# bmsMaster_usb.net
KiCad netlist of a schematic drawn in Altium Designer
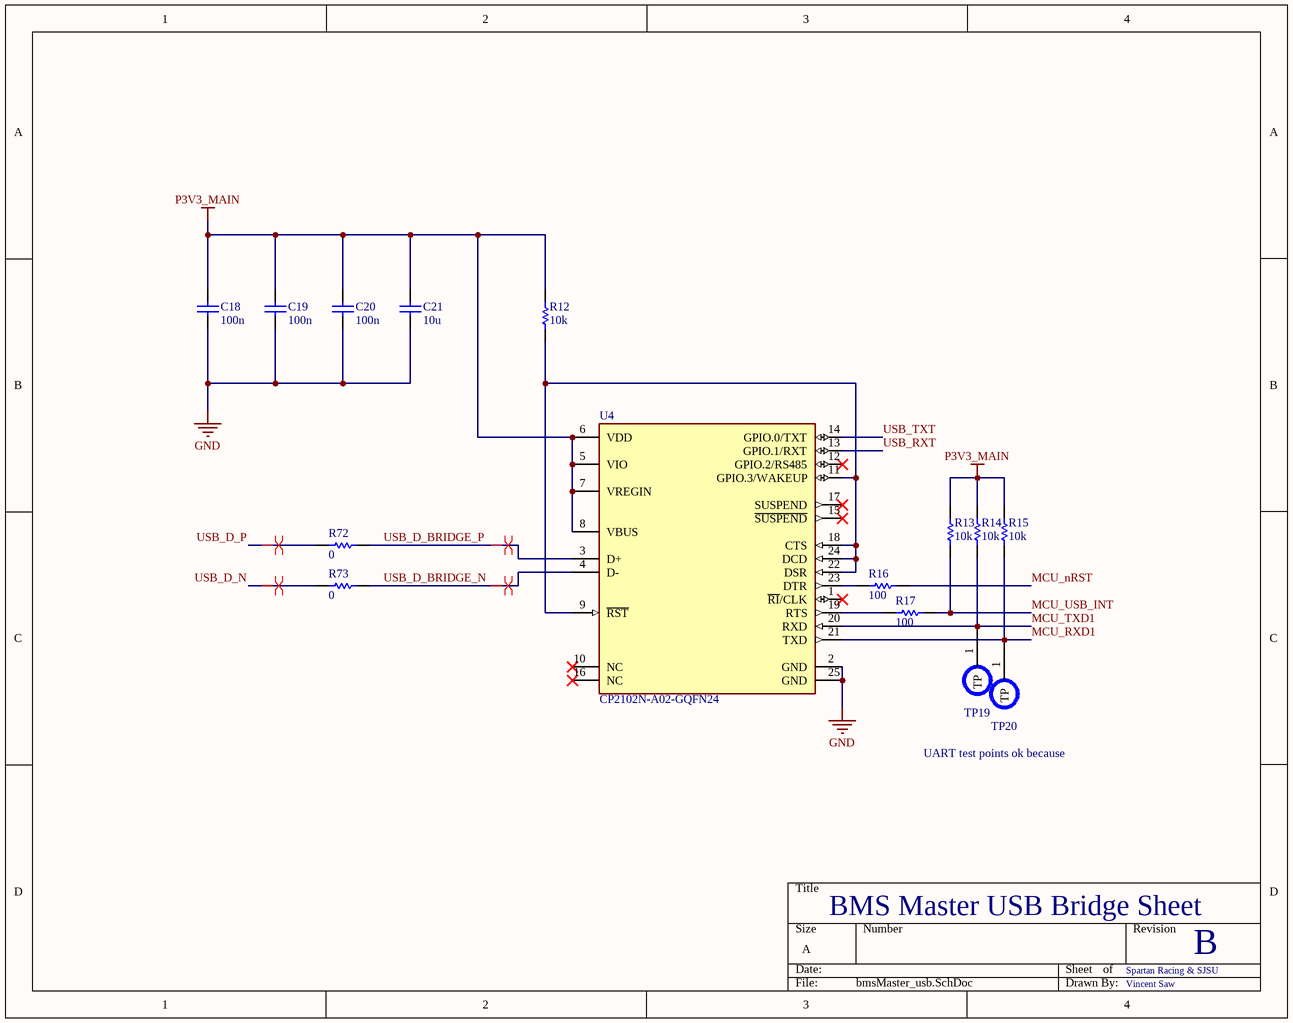
[diagram p0: bmsMaster_usb.SchDoc]

(export (version "E")
  (design (tool "Eeschema 10.0.6"))
  (components
    (comp (ref "C18")
      (value "100n")
      (footprint "CAPC1608X90N")
      (description "Capacitor")
      (libsource (lib "Simulation Generic Components") (part "Capacitor"))
    )
    (comp (ref "C19")
      (value "100n")
      (footprint "CAPC1608X90N")
      (description "Capacitor")
      (libsource (lib "Simulation Generic Components") (part "Capacitor"))
    )
    (comp (ref "C20")
      (value "100n")
      (footprint "CAPC1608X90N")
      (description "Capacitor")
      (libsource (lib "Simulation Generic Components") (part "Capacitor"))
    )
    (comp (ref "C21")
      (value "10u")
      (footprint "CAPC1608X90N")
      (description "Capacitor")
      (libsource (lib "Simulation Generic Components") (part "Capacitor"))
    )
    (comp (ref "R12")
      (value "10k")
      (footprint "RESC1608X50N")
      (description "Resistor")
      (libsource (lib "Simulation Generic Components") (part "Resistor"))
    )
    (comp (ref "R13")
      (value "10k")
      (footprint "RESC1608X50N")
      (description "Resistor")
      (libsource (lib "Simulation Generic Components") (part "Resistor"))
    )
    (comp (ref "R14")
      (value "10k")
      (footprint "RESC1608X50N")
      (description "Resistor")
      (libsource (lib "Simulation Generic Components") (part "Resistor"))
    )
    (comp (ref "R15")
      (value "10k")
      (footprint "RESC1608X50N")
      (description "Resistor")
      (libsource (lib "Simulation Generic Components") (part "Resistor"))
    )
    (comp (ref "R16")
      (value "100")
      (footprint "RESC1608X50N")
      (description "Resistor")
      (libsource (lib "Simulation Generic Components") (part "Resistor"))
    )
    (comp (ref "R17")
      (value "100")
      (footprint "RESC1608X50N")
      (description "Resistor")
      (libsource (lib "Simulation Generic Components") (part "Resistor"))
    )
    (comp (ref "R72")
      (value "0")
      (footprint "RESC1608X50N")
      (description "Resistor")
      (libsource (lib "Simulation Generic Components") (part "Resistor"))
    )
    (comp (ref "R73")
      (value "0")
      (footprint "RESC1608X50N")
      (description "Resistor")
      (libsource (lib "Simulation Generic Components") (part "Resistor"))
    )
    (comp (ref "TP19")
      (value "TSTPT")
      (footprint "Testpoint1")
      (libsource (lib "testpoint1") (part "Testpoint1"))
    )
    (comp (ref "TP20")
      (value "TSTPT")
      (footprint "Testpoint1")
      (libsource (lib "testpoint1") (part "Testpoint1"))
    )
    (comp (ref "U4")
      (value "CP2102N-A02-GQFN24")
      (footprint "FP-CP2102N-A02-GQFN24-MFG")
      (description "IC USB TO UART BRIDGE QFN24")
      (libsource (lib "Altium Content Vault") (part "132705adcabca70c0fc25feb25b66a0"))
    )
  )
  (nets
    (net (code "1") (name "/MCU_RXD1") (class "Default")
      (node (ref "R15") (pin "1") (pinfunction "1_1") (pintype "passive"))
      (node (ref "TP20") (pin "1") (pinfunction "TP_1") (pintype "passive"))
      (node (ref "U4") (pin "21") (pinfunction "TXD_21") (pintype "output"))
    )
    (net (code "2") (name "/MCU_TXD1") (class "Default")
      (node (ref "R14") (pin "1") (pinfunction "1_1") (pintype "passive"))
      (node (ref "TP19") (pin "1") (pinfunction "TP_1") (pintype "passive"))
      (node (ref "U4") (pin "20") (pinfunction "RXD_20") (pintype "input"))
    )
    (net (code "3") (name "/MCU_USB_INT") (class "Default")
      (node (ref "R13") (pin "1") (pinfunction "1_1") (pintype "passive"))
      (node (ref "R17") (pin "1") (pinfunction "1_1") (pintype "passive"))
    )
    (net (code "4") (name "/MCU_nRST") (class "Default")
      (node (ref "R16") (pin "1") (pinfunction "1_1") (pintype "passive"))
    )
    (net (code "5") (name "/USB_D_BRIDGE_N") (class "Default")
      (node (ref "R73") (pin "2") (pinfunction "2_2") (pintype "passive"))
      (node (ref "U4") (pin "4") (pinfunction "D-_4") (pintype "passive"))
    )
    (net (code "6") (name "/USB_D_BRIDGE_P") (class "Default")
      (node (ref "R72") (pin "2") (pinfunction "2_2") (pintype "passive"))
      (node (ref "U4") (pin "3") (pinfunction "D+_3") (pintype "passive"))
    )
    (net (code "7") (name "/USB_D_N") (class "Default")
      (node (ref "R73") (pin "1") (pinfunction "1_1") (pintype "passive"))
    )
    (net (code "8") (name "/USB_D_P") (class "Default")
      (node (ref "R72") (pin "1") (pinfunction "1_1") (pintype "passive"))
    )
    (net (code "9") (name "/USB_RXT") (class "Default")
      (node (ref "U4") (pin "13") (pinfunction "GPIO.1/RXT_13") (pintype "bidirectional"))
    )
    (net (code "10") (name "/USB_TXT") (class "Default")
      (node (ref "U4") (pin "14") (pinfunction "GPIO.0/TXT_14") (pintype "bidirectional"))
    )
    (net (code "11") (name "GND") (class "Default")
      (node (ref "C18") (pin "1") (pinfunction "1_1") (pintype "passive"))
      (node (ref "C19") (pin "1") (pinfunction "1_1") (pintype "passive"))
      (node (ref "C20") (pin "1") (pinfunction "1_1") (pintype "passive"))
      (node (ref "C21") (pin "1") (pinfunction "1_1") (pintype "passive"))
      (node (ref "U4") (pin "2") (pinfunction "GND_2") (pintype "power_in"))
      (node (ref "U4") (pin "25") (pinfunction "GND_25") (pintype "power_in"))
    )
    (net (code "12") (name "Net-(U4-CTS)") (class "Default")
      (node (ref "R12") (pin "1") (pinfunction "1_1") (pintype "passive"))
      (node (ref "U4") (pin "11") (pinfunction "GPIO.3/WAKEUP_11") (pintype "bidirectional"))
      (node (ref "U4") (pin "18") (pinfunction "CTS_18") (pintype "input"))
      (node (ref "U4") (pin "22") (pinfunction "DSR_22") (pintype "input"))
      (node (ref "U4") (pin "24") (pinfunction "DCD_24") (pintype "input"))
      (node (ref "U4") (pin "9") (pinfunction "~{RST}_9") (pintype "input"))
    )
    (net (code "13") (name "Net-(U4-DTR)") (class "Default")
      (node (ref "R16") (pin "2") (pinfunction "2_2") (pintype "passive"))
      (node (ref "U4") (pin "23") (pinfunction "DTR_23") (pintype "output"))
    )
    (net (code "14") (name "Net-(U4-RTS)") (class "Default")
      (node (ref "R17") (pin "2") (pinfunction "2_2") (pintype "passive"))
      (node (ref "U4") (pin "19") (pinfunction "RTS_19") (pintype "output"))
    )
    (net (code "15") (name "P3V3_MAIN") (class "Default")
      (node (ref "C18") (pin "2") (pinfunction "2_2") (pintype "passive"))
      (node (ref "C19") (pin "2") (pinfunction "2_2") (pintype "passive"))
      (node (ref "C20") (pin "2") (pinfunction "2_2") (pintype "passive"))
      (node (ref "C21") (pin "2") (pinfunction "2_2") (pintype "passive"))
      (node (ref "R12") (pin "2") (pinfunction "2_2") (pintype "passive"))
      (node (ref "R13") (pin "2") (pinfunction "2_2") (pintype "passive"))
      (node (ref "R14") (pin "2") (pinfunction "2_2") (pintype "passive"))
      (node (ref "R15") (pin "2") (pinfunction "2_2") (pintype "passive"))
      (node (ref "U4") (pin "5") (pinfunction "VIO_5") (pintype "power_in"))
      (node (ref "U4") (pin "6") (pinfunction "VDD_6") (pintype "power_in"))
      (node (ref "U4") (pin "7") (pinfunction "VREGIN_7") (pintype "power_in"))
      (node (ref "U4") (pin "8") (pinfunction "VBUS_8") (pintype "power_in"))
    )
    (net (code "16") (name "unconnected-(U4-GPIO.2{slash}RS485-Pad12)") (class "Default")
      (node (ref "U4") (pin "12") (pinfunction "GPIO.2/RS485_12") (pintype "bidirectional+no_connect"))
    )
    (net (code "17") (name "unconnected-(U4-NC-Pad10)") (class "Default")
      (node (ref "U4") (pin "10") (pinfunction "NC_10") (pintype "passive+no_connect"))
    )
    (net (code "18") (name "unconnected-(U4-NC-Pad16)") (class "Default")
      (node (ref "U4") (pin "16") (pinfunction "NC_16") (pintype "passive+no_connect"))
    )
    (net (code "19") (name "unconnected-(U4-SUSPEND-Pad17)") (class "Default")
      (node (ref "U4") (pin "17") (pinfunction "SUSPEND_17") (pintype "output+no_connect"))
    )
    (net (code "20") (name "unconnected-(U4-~{RI}{slash}CLK-Pad1)") (class "Default")
      (node (ref "U4") (pin "1") (pinfunction "~{RI}/CLK_1") (pintype "bidirectional+no_connect"))
    )
    (net (code "21") (name "unconnected-(U4-~{SUSPEND}-Pad15)") (class "Default")
      (node (ref "U4") (pin "15") (pinfunction "~{SUSPEND}_15") (pintype "output+no_connect"))
    )
  )
)
